# openenergy.net
KiCad netlist of a schematic drawn in EAGLE
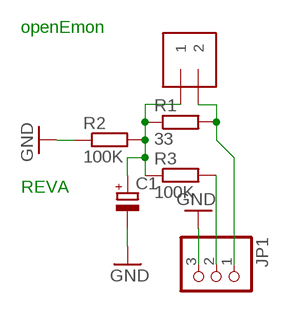
[diagram p0: schematic, sheet 1]

(export (version "E")
  (design (tool "Eeschema 10.0.6"))
  (components
    (comp (ref "C1")
      (value "CPOL-EUB45181A")
      (footprint "eagle-import:B45181A")
      (libsource (lib "eagle-import") (part "CPOL-EUB45181A"))
    )
    (comp (ref "J1")
      (value "1X2-3.5MM")
      (footprint "eagle-import:1X2-3.5MM")
      (libsource (lib "eagle-import") (part "1X2-3.5MM"))
    )
    (comp (ref "JP1")
      (value "PINHD-1X3")
      (footprint "eagle-import:1X03")
      (libsource (lib "eagle-import") (part "PINHD-1X3"))
    )
    (comp (ref "R1")
      (value "33")
      (footprint "eagle-import:0204_5")
      (libsource (lib "eagle-import") (part "R-EU_0204/5"))
    )
    (comp (ref "R2")
      (value "100K")
      (footprint "eagle-import:0204_5")
      (libsource (lib "eagle-import") (part "R-EU_0204/5"))
    )
    (comp (ref "R3")
      (value "100K")
      (footprint "eagle-import:0204_5")
      (libsource (lib "eagle-import") (part "R-EU_0204/5"))
    )
  )
  (nets
    (net (code "1") (name "GND") (class "Default")
      (node (ref "C1") (pin "-") (pinfunction "-_-") (pintype "passive"))
      (node (ref "JP1") (pin "3") (pinfunction "3_3") (pintype "passive"))
      (node (ref "R2") (pin "1") (pinfunction "1_1") (pintype "passive"))
    )
    (net (code "2") (name "Net-(C1-Pad+)") (class "Default")
      (node (ref "C1") (pin "+") (pinfunction "+_+") (pintype "passive"))
      (node (ref "J1") (pin "1") (pinfunction "1_1") (pintype "passive"))
      (node (ref "R1") (pin "1") (pinfunction "1_1") (pintype "passive"))
      (node (ref "R2") (pin "2") (pinfunction "2_2") (pintype "passive"))
      (node (ref "R3") (pin "1") (pinfunction "1_1") (pintype "passive"))
    )
    (net (code "3") (name "Net-(J1-Pad2)") (class "Default")
      (node (ref "J1") (pin "2") (pinfunction "2_2") (pintype "passive"))
      (node (ref "JP1") (pin "1") (pinfunction "1_1") (pintype "passive"))
      (node (ref "R1") (pin "2") (pinfunction "2_2") (pintype "passive"))
    )
    (net (code "4") (name "Net-(JP1-Pad2)") (class "Default")
      (node (ref "JP1") (pin "2") (pinfunction "2_2") (pintype "passive"))
      (node (ref "R3") (pin "2") (pinfunction "2_2") (pintype "passive"))
    )
  )
)
